# BalancedInputOutput.net
KiCad netlist of a schematic drawn in EAGLE
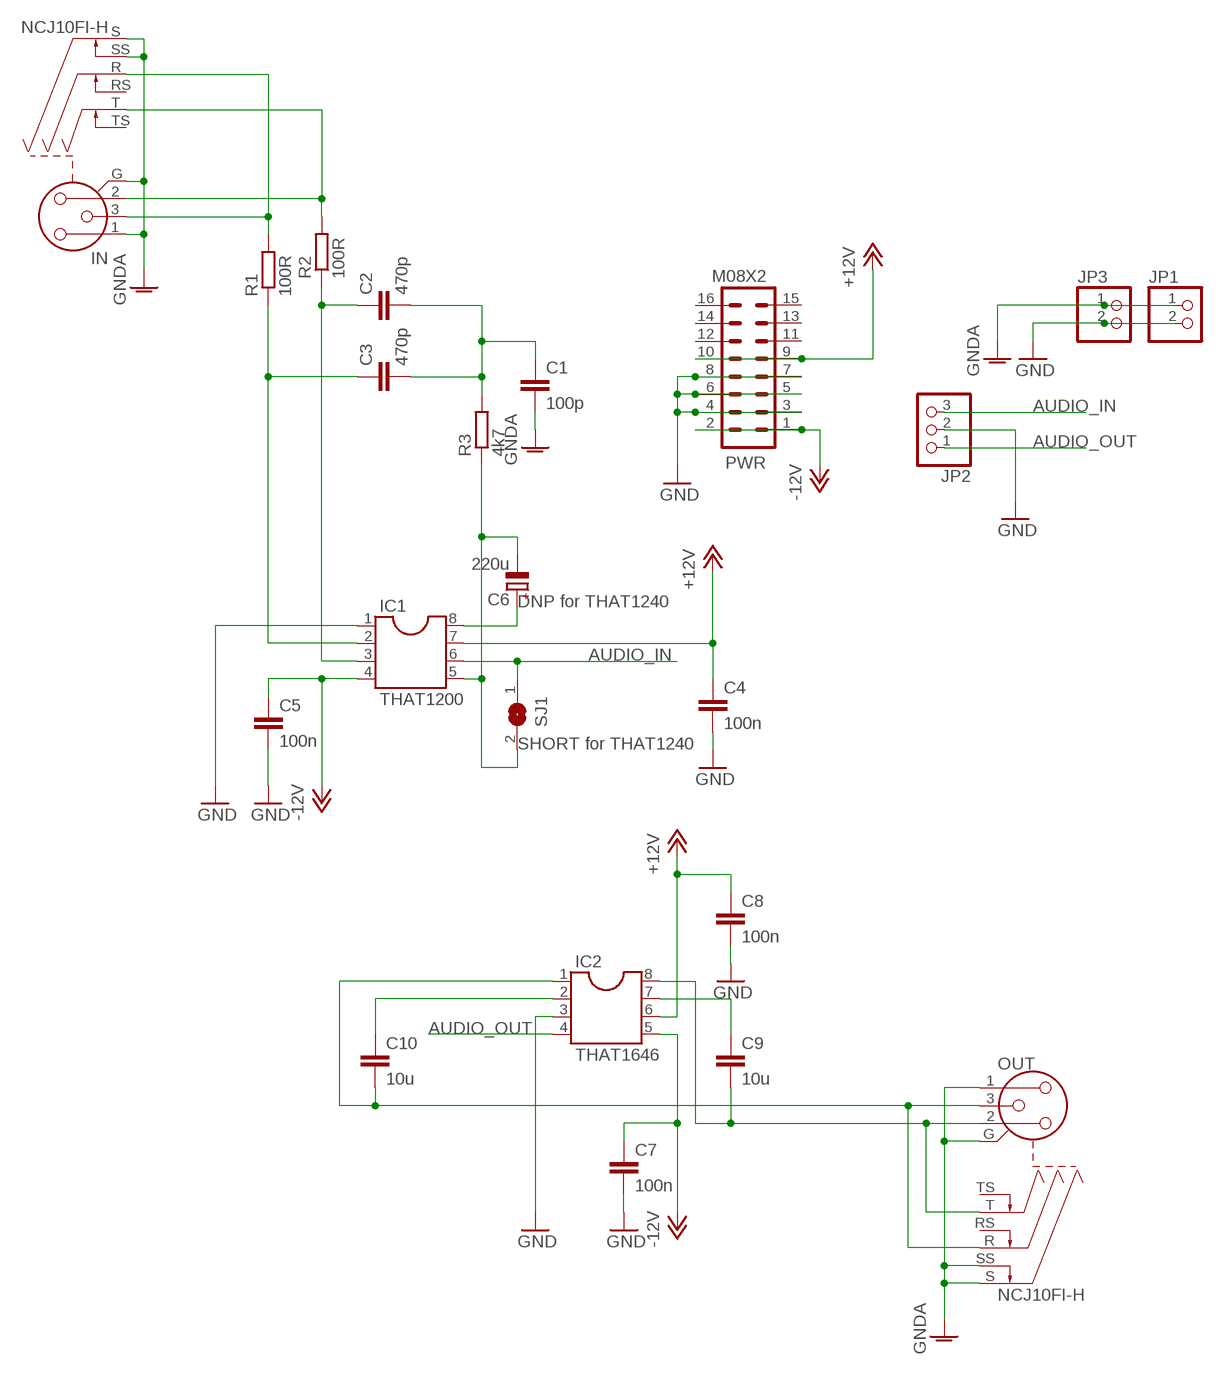
[diagram p0: schematic, sheet 1]

(export (version "E")
  (design (tool "Eeschema 10.0.6"))
  (components
    (comp (ref "C1")
      (value "100p")
      (footprint "eagle-import:C050-025X075")
      (libsource (lib "eagle-import") (part "C-EU050-025X075"))
    )
    (comp (ref "C2")
      (value "470p")
      (footprint "eagle-import:C050-025X075")
      (libsource (lib "eagle-import") (part "C-EU050-025X075"))
    )
    (comp (ref "C3")
      (value "470p")
      (footprint "eagle-import:C050-025X075")
      (libsource (lib "eagle-import") (part "C-EU050-025X075"))
    )
    (comp (ref "C4")
      (value "100n")
      (footprint "eagle-import:C050-025X075")
      (libsource (lib "eagle-import") (part "C-EU050-025X075"))
    )
    (comp (ref "C5")
      (value "100n")
      (footprint "eagle-import:C050-025X075")
      (libsource (lib "eagle-import") (part "C-EU050-025X075"))
    )
    (comp (ref "C6")
      (value "220u")
      (footprint "eagle-import:E5-8,5")
      (libsource (lib "eagle-import") (part "CPOL-EUE5-8.5"))
    )
    (comp (ref "C7")
      (value "100n")
      (footprint "eagle-import:C050-025X075")
      (libsource (lib "eagle-import") (part "C-EU050-025X075"))
    )
    (comp (ref "C8")
      (value "100n")
      (footprint "eagle-import:C050-025X075")
      (libsource (lib "eagle-import") (part "C-EU050-025X075"))
    )
    (comp (ref "C9")
      (value "10u")
      (footprint "eagle-import:C050-025X075")
      (libsource (lib "eagle-import") (part "C-EU050-025X075"))
    )
    (comp (ref "C10")
      (value "10u")
      (footprint "eagle-import:C050-025X075")
      (libsource (lib "eagle-import") (part "C-EU050-025X075"))
    )
    (comp (ref "IC1")
      (value "THAT1200")
      (footprint "eagle-import:DIL08")
      (libsource (lib "eagle-import") (part "DIL8"))
    )
    (comp (ref "IC2")
      (value "THAT1646")
      (footprint "eagle-import:DIL08")
      (libsource (lib "eagle-import") (part "DIL8"))
    )
    (comp (ref "IN")
      (value "NCJ10FI-H")
      (footprint "eagle-import:NCJ10FI-H")
      (libsource (lib "eagle-import") (part "NCJ10FI-H"))
    )
    (comp (ref "JP1")
      (value "PINHD-1X2")
      (footprint "eagle-import:1X02")
      (libsource (lib "eagle-import") (part "PINHD-1X2"))
    )
    (comp (ref "JP2")
      (value "PINHD-1X3")
      (footprint "eagle-import:1X03")
      (libsource (lib "eagle-import") (part "PINHD-1X3"))
    )
    (comp (ref "JP3")
      (value "PINHD-1X2")
      (footprint "eagle-import:1X02")
      (libsource (lib "eagle-import") (part "PINHD-1X2"))
    )
    (comp (ref "OUT")
      (value "NCJ10FI-H")
      (footprint "eagle-import:NCJ10FI-H")
      (libsource (lib "eagle-import") (part "NCJ10FI-H"))
    )
    (comp (ref "PWR")
      (value "M08X2")
      (footprint "eagle-import:2X8")
      (libsource (lib "eagle-import") (part "M08X2"))
    )
    (comp (ref "R1")
      (value "100R")
      (footprint "eagle-import:0207_7")
      (libsource (lib "eagle-import") (part "R-EU_0207/7"))
    )
    (comp (ref "R2")
      (value "100R")
      (footprint "eagle-import:0207_7")
      (libsource (lib "eagle-import") (part "R-EU_0207/7"))
    )
    (comp (ref "R3")
      (value "4k7")
      (footprint "eagle-import:0207_7")
      (libsource (lib "eagle-import") (part "R-EU_0207/7"))
    )
    (comp (ref "SJ1")
      (value "SJW")
      (footprint "eagle-import:SJW")
      (libsource (lib "eagle-import") (part "SJW"))
    )
  )
  (nets
    (net (code "1") (name "+12V") (class "Default")
      (node (ref "C4") (pin "1") (pinfunction "1_1") (pintype "passive"))
      (node (ref "C8") (pin "1") (pinfunction "1_1") (pintype "passive"))
      (node (ref "IC1") (pin "7") (pinfunction "7_7") (pintype "passive"))
      (node (ref "IC2") (pin "6") (pinfunction "6_6") (pintype "passive"))
      (node (ref "PWR") (pin "10") (pinfunction "10_10") (pintype "passive"))
      (node (ref "PWR") (pin "9") (pinfunction "9_9") (pintype "passive"))
    )
    (net (code "2") (name "-12V") (class "Default")
      (node (ref "C5") (pin "1") (pinfunction "1_1") (pintype "passive"))
      (node (ref "C7") (pin "1") (pinfunction "1_1") (pintype "passive"))
      (node (ref "IC1") (pin "4") (pinfunction "4_4") (pintype "passive"))
      (node (ref "IC2") (pin "5") (pinfunction "5_5") (pintype "passive"))
      (node (ref "PWR") (pin "1") (pinfunction "1_1") (pintype "passive"))
      (node (ref "PWR") (pin "2") (pinfunction "2_2") (pintype "passive"))
    )
    (net (code "3") (name "/AUDIO_IN") (class "Default")
      (node (ref "IC1") (pin "6") (pinfunction "6_6") (pintype "passive"))
      (node (ref "JP2") (pin "3") (pinfunction "3_3") (pintype "passive"))
      (node (ref "SJ1") (pin "1") (pinfunction "1_1") (pintype "passive"))
    )
    (net (code "4") (name "/AUDIO_OUT") (class "Default")
      (node (ref "IC2") (pin "4") (pinfunction "4_4") (pintype "passive"))
      (node (ref "JP2") (pin "1") (pinfunction "1_1") (pintype "passive"))
    )
    (net (code "5") (name "GND") (class "Default")
      (node (ref "C4") (pin "2") (pinfunction "2_2") (pintype "passive"))
      (node (ref "C5") (pin "2") (pinfunction "2_2") (pintype "passive"))
      (node (ref "C7") (pin "2") (pinfunction "2_2") (pintype "passive"))
      (node (ref "C8") (pin "2") (pinfunction "2_2") (pintype "passive"))
      (node (ref "IC1") (pin "1") (pinfunction "1_1") (pintype "passive"))
      (node (ref "IC2") (pin "3") (pinfunction "3_3") (pintype "passive"))
      (node (ref "JP1") (pin "2") (pinfunction "2_2") (pintype "passive"))
      (node (ref "JP2") (pin "2") (pinfunction "2_2") (pintype "passive"))
      (node (ref "JP3") (pin "2") (pinfunction "2_2") (pintype "passive"))
      (node (ref "PWR") (pin "3") (pinfunction "3_3") (pintype "passive"))
      (node (ref "PWR") (pin "4") (pinfunction "4_4") (pintype "passive"))
      (node (ref "PWR") (pin "5") (pinfunction "5_5") (pintype "passive"))
      (node (ref "PWR") (pin "6") (pinfunction "6_6") (pintype "passive"))
      (node (ref "PWR") (pin "7") (pinfunction "7_7") (pintype "passive"))
      (node (ref "PWR") (pin "8") (pinfunction "8_8") (pintype "passive"))
    )
    (net (code "6") (name "GNDA") (class "Default")
      (node (ref "C1") (pin "2") (pinfunction "2_2") (pintype "passive"))
      (node (ref "IN") (pin "1") (pinfunction "1_1") (pintype "passive"))
      (node (ref "IN") (pin "G") (pinfunction "G_G") (pintype "passive"))
      (node (ref "IN") (pin "S") (pinfunction "S_S") (pintype "passive"))
      (node (ref "IN") (pin "SS") (pinfunction "SS_SS") (pintype "passive"))
      (node (ref "JP1") (pin "1") (pinfunction "1_1") (pintype "passive"))
      (node (ref "JP3") (pin "1") (pinfunction "1_1") (pintype "passive"))
      (node (ref "OUT") (pin "1") (pinfunction "1_1") (pintype "passive"))
      (node (ref "OUT") (pin "G") (pinfunction "G_G") (pintype "passive"))
      (node (ref "OUT") (pin "S") (pinfunction "S_S") (pintype "passive"))
      (node (ref "OUT") (pin "SS") (pinfunction "SS_SS") (pintype "passive"))
    )
    (net (code "7") (name "Net-(C1-Pad1)") (class "Default")
      (node (ref "C1") (pin "1") (pinfunction "1_1") (pintype "passive"))
      (node (ref "C2") (pin "2") (pinfunction "2_2") (pintype "passive"))
      (node (ref "C3") (pin "2") (pinfunction "2_2") (pintype "passive"))
      (node (ref "R3") (pin "2") (pinfunction "2_2") (pintype "passive"))
    )
    (net (code "8") (name "Net-(C2-Pad1)") (class "Default")
      (node (ref "C2") (pin "1") (pinfunction "1_1") (pintype "passive"))
      (node (ref "IC1") (pin "3") (pinfunction "3_3") (pintype "passive"))
      (node (ref "R2") (pin "1") (pinfunction "1_1") (pintype "passive"))
    )
    (net (code "9") (name "Net-(C3-Pad1)") (class "Default")
      (node (ref "C3") (pin "1") (pinfunction "1_1") (pintype "passive"))
      (node (ref "IC1") (pin "2") (pinfunction "2_2") (pintype "passive"))
      (node (ref "R1") (pin "1") (pinfunction "1_1") (pintype "passive"))
    )
    (net (code "10") (name "Net-(C6-Pad+)") (class "Default")
      (node (ref "C6") (pin "+") (pinfunction "+_+") (pintype "passive"))
      (node (ref "IC1") (pin "8") (pinfunction "8_8") (pintype "passive"))
    )
    (net (code "11") (name "Net-(C6-Pad-)") (class "Default")
      (node (ref "C6") (pin "-") (pinfunction "-_-") (pintype "passive"))
      (node (ref "IC1") (pin "5") (pinfunction "5_5") (pintype "passive"))
      (node (ref "R3") (pin "1") (pinfunction "1_1") (pintype "passive"))
      (node (ref "SJ1") (pin "2") (pinfunction "2_2") (pintype "passive"))
    )
    (net (code "12") (name "Net-(C9-Pad1)") (class "Default")
      (node (ref "C9") (pin "1") (pinfunction "1_1") (pintype "passive"))
      (node (ref "IC2") (pin "7") (pinfunction "7_7") (pintype "passive"))
    )
    (net (code "13") (name "Net-(C9-Pad2)") (class "Default")
      (node (ref "C9") (pin "2") (pinfunction "2_2") (pintype "passive"))
      (node (ref "IC2") (pin "8") (pinfunction "8_8") (pintype "passive"))
      (node (ref "OUT") (pin "2") (pinfunction "2_2") (pintype "passive"))
      (node (ref "OUT") (pin "T") (pinfunction "T_T") (pintype "passive"))
    )
    (net (code "14") (name "Net-(C10-Pad1)") (class "Default")
      (node (ref "C10") (pin "1") (pinfunction "1_1") (pintype "passive"))
      (node (ref "IC2") (pin "2") (pinfunction "2_2") (pintype "passive"))
    )
    (net (code "15") (name "Net-(C10-Pad2)") (class "Default")
      (node (ref "C10") (pin "2") (pinfunction "2_2") (pintype "passive"))
      (node (ref "IC2") (pin "1") (pinfunction "1_1") (pintype "passive"))
      (node (ref "OUT") (pin "3") (pinfunction "3_3") (pintype "passive"))
      (node (ref "OUT") (pin "R") (pinfunction "R_R") (pintype "passive"))
    )
    (net (code "16") (name "Net-(IN-Pad2)") (class "Default")
      (node (ref "IN") (pin "2") (pinfunction "2_2") (pintype "passive"))
      (node (ref "IN") (pin "T") (pinfunction "T_T") (pintype "passive"))
      (node (ref "R2") (pin "2") (pinfunction "2_2") (pintype "passive"))
    )
    (net (code "17") (name "Net-(IN-Pad3)") (class "Default")
      (node (ref "IN") (pin "3") (pinfunction "3_3") (pintype "passive"))
      (node (ref "IN") (pin "R") (pinfunction "R_R") (pintype "passive"))
      (node (ref "R1") (pin "2") (pinfunction "2_2") (pintype "passive"))
    )
    (net (code "18") (name "unconnected-(IN-PadRS)") (class "Default")
      (node (ref "IN") (pin "RS") (pinfunction "RS_RS") (pintype "passive"))
    )
    (net (code "19") (name "unconnected-(IN-PadTS)") (class "Default")
      (node (ref "IN") (pin "TS") (pinfunction "TS_TS") (pintype "passive"))
    )
    (net (code "20") (name "unconnected-(OUT-PadRS)") (class "Default")
      (node (ref "OUT") (pin "RS") (pinfunction "RS_RS") (pintype "passive"))
    )
    (net (code "21") (name "unconnected-(OUT-PadTS)") (class "Default")
      (node (ref "OUT") (pin "TS") (pinfunction "TS_TS") (pintype "passive"))
    )
    (net (code "22") (name "unconnected-(PWR-Pad11)") (class "Default")
      (node (ref "PWR") (pin "11") (pinfunction "11_11") (pintype "passive"))
    )
    (net (code "23") (name "unconnected-(PWR-Pad12)") (class "Default")
      (node (ref "PWR") (pin "12") (pinfunction "12_12") (pintype "passive"))
    )
    (net (code "24") (name "unconnected-(PWR-Pad13)") (class "Default")
      (node (ref "PWR") (pin "13") (pinfunction "13_13") (pintype "passive"))
    )
    (net (code "25") (name "unconnected-(PWR-Pad14)") (class "Default")
      (node (ref "PWR") (pin "14") (pinfunction "14_14") (pintype "passive"))
    )
    (net (code "26") (name "unconnected-(PWR-Pad15)") (class "Default")
      (node (ref "PWR") (pin "15") (pinfunction "15_15") (pintype "passive"))
    )
    (net (code "27") (name "unconnected-(PWR-Pad16)") (class "Default")
      (node (ref "PWR") (pin "16") (pinfunction "16_16") (pintype "passive"))
    )
  )
)
